# nRF24L01.net
KiCad netlist of a schematic drawn in Altium Designer
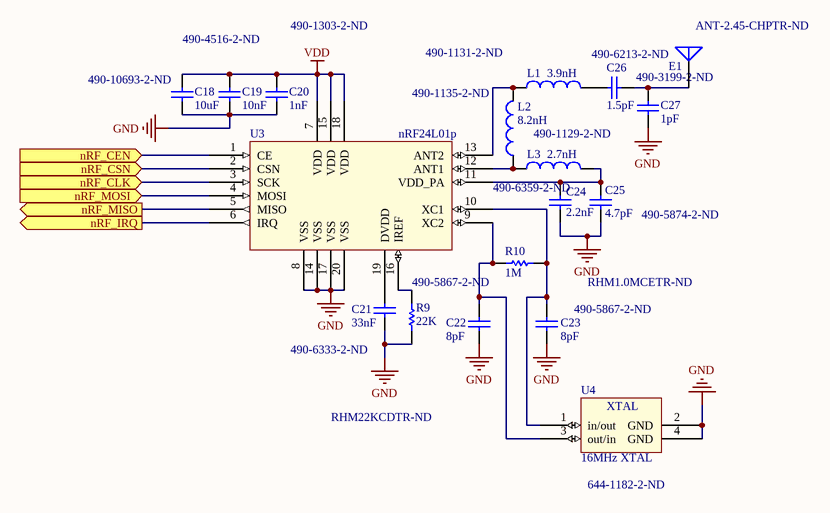
[diagram p0: nRF24L01.SchDoc]

(export (version "E")
  (design (tool "Eeschema 10.0.6"))
  (components
    (comp (ref "C18")
      (value "10uF")
      (footprint "0402")
      (description "Capacitor (Semiconductor SIM Model)")
      (fields
        (field (name "SUPPLIER PART NUMBER 1") "490-10693-2-ND")
        (field (name "PUBLISHER") "Altium Limited")
      )
      (libsource (lib "Miscellaneous Devices") (part "Cap Semi"))
    )
    (comp (ref "C19")
      (value "10nF")
      (footprint "0402")
      (description "Capacitor (Semiconductor SIM Model)")
      (fields
        (field (name "SUPPLIER PART NUMBER 1") "490-4516-2-ND")
        (field (name "PUBLISHER") "Altium Limited")
      )
      (libsource (lib "Miscellaneous Devices") (part "Cap Semi"))
    )
    (comp (ref "C20")
      (value "1nF")
      (footprint "0402")
      (description "Capacitor (Semiconductor SIM Model)")
      (fields
        (field (name "SUPPLIER PART NUMBER 1") "490-1303-2-ND")
        (field (name "PUBLISHER") "Altium Limited")
      )
      (libsource (lib "Miscellaneous Devices") (part "Cap Semi"))
    )
    (comp (ref "C21")
      (value "33nF")
      (footprint "0402")
      (description "Capacitor (Semiconductor SIM Model)")
      (fields
        (field (name "SUPPLIER PART NUMBER 1") "490-6333-2-ND")
        (field (name "PUBLISHER") "Altium Limited")
      )
      (libsource (lib "Miscellaneous Devices") (part "Cap Semi"))
    )
    (comp (ref "C22")
      (value "8pF")
      (footprint "0402")
      (description "Capacitor (Semiconductor SIM Model)")
      (fields
        (field (name "SUPPLIER PART NUMBER 1") "490-5867-2-ND")
        (field (name "PUBLISHER") "Altium Limited")
      )
      (libsource (lib "Miscellaneous Devices") (part "Cap Semi"))
    )
    (comp (ref "C23")
      (value "8pF")
      (footprint "0402")
      (description "Capacitor (Semiconductor SIM Model)")
      (fields
        (field (name "SUPPLIER PART NUMBER 1") "490-5867-2-ND")
        (field (name "PUBLISHER") "Altium Limited")
      )
      (libsource (lib "Miscellaneous Devices") (part "Cap Semi"))
    )
    (comp (ref "C24")
      (value "2.2nF")
      (footprint "0402")
      (description "Capacitor (Semiconductor SIM Model)")
      (fields
        (field (name "SUPPLIER PART NUMBER 1") "490-6359-2-ND")
        (field (name "PUBLISHER") "Altium Limited")
      )
      (libsource (lib "Miscellaneous Devices") (part "Cap Semi"))
    )
    (comp (ref "C25")
      (value "4.7pF")
      (footprint "0402")
      (description "Capacitor (Semiconductor SIM Model)")
      (fields
        (field (name "SUPPLIER PART NUMBER 1") "490-5874-2-ND")
        (field (name "PUBLISHER") "Altium Limited")
      )
      (libsource (lib "Miscellaneous Devices") (part "Cap Semi"))
    )
    (comp (ref "C26")
      (value "1.5pF")
      (footprint "0402")
      (description "Capacitor (Semiconductor SIM Model)")
      (fields
        (field (name "SUPPLIER PART NUMBER 1") "490-6213-2-ND")
        (field (name "PUBLISHER") "Altium Limited")
      )
      (libsource (lib "Miscellaneous Devices") (part "Cap Semi"))
    )
    (comp (ref "C27")
      (value "1pF")
      (footprint "0402")
      (description "Capacitor (Semiconductor SIM Model)")
      (fields
        (field (name "SUPPLIER PART NUMBER 1") "490-3199-2-ND")
        (field (name "PUBLISHER") "Altium Limited")
      )
      (libsource (lib "Miscellaneous Devices") (part "Cap Semi"))
    )
    (comp (ref "E1")
      (value "~")
      (footprint "ANT-2.45-CHP-B")
      (description "Generic Antenna")
      (fields
        (field (name "SUPPLIER PART NUMBER 1") "ANT-2.45-CHPTR-ND")
        (field (name "PUBLISHER") "Altium Limited")
      )
      (libsource (lib "Miscellaneous Devices") (part "Antenna"))
    )
    (comp (ref "L1")
      (value "3.9nH")
      (footprint "0402")
      (description "Inductor")
      (fields
        (field (name "SUPPLIER PART NUMBER 1") "490-1131-2-ND")
        (field (name "PUBLISHER") "Altium Limited")
      )
      (libsource (lib "Miscellaneous Devices") (part "Inductor"))
    )
    (comp (ref "L2")
      (value "8.2nH")
      (footprint "0402")
      (description "Inductor")
      (fields
        (field (name "SUPPLIER PART NUMBER 1") "490-1135-2-ND")
        (field (name "PUBLISHER") "Altium Limited")
      )
      (libsource (lib "Miscellaneous Devices") (part "Inductor"))
    )
    (comp (ref "L3")
      (value "2.7nH")
      (footprint "0402")
      (description "Inductor")
      (fields
        (field (name "SUPPLIER PART NUMBER 1") "490-1129-2-ND")
        (field (name "PUBLISHER") "Altium Limited")
      )
      (libsource (lib "Miscellaneous Devices") (part "Inductor"))
    )
    (comp (ref "R9")
      (value "22K")
      (footprint "0402")
      (description "Semiconductor Resistor")
      (fields
        (field (name "SUPPLIER PART NUMBER 1") "RHM22KCDTR-ND")
        (field (name "PUBLISHER") "Altium Limited")
      )
      (libsource (lib "Miscellaneous Devices") (part "Res Semi"))
    )
    (comp (ref "R10")
      (value "1M")
      (footprint "0402")
      (description "Semiconductor Resistor")
      (fields
        (field (name "SUPPLIER PART NUMBER 1") "RHM1.0MCETR-ND")
        (field (name "PUBLISHER") "Altium Limited")
      )
      (libsource (lib "Miscellaneous Devices") (part "Res Semi"))
    )
    (comp (ref "U3")
      (value "nRF24L01p")
      (footprint "Component_nRF")
      (libsource (lib "nRF24L01") (part "Component_nRF"))
    )
    (comp (ref "U4")
      (value "16MHz XTAL")
      (footprint "8Y-16.000MAAV-T")
      (description "SMD 16 MHz XTAL")
      (fields (field (name "SUPPLIER PART NUMBER 1") "644-1182-2-ND"))
      (libsource (lib "headstage_parts") (part "8Y-16.000MAAV-T"))
    )
  )
  (nets
    (net (code "1") (name "/nRF_CEN") (class "Default")
      (node (ref "U3") (pin "1") (pinfunction "CE_1") (pintype "input"))
    )
    (net (code "2") (name "/nRF_CLK") (class "Default")
      (node (ref "U3") (pin "3") (pinfunction "SCK_3") (pintype "input"))
    )
    (net (code "3") (name "/nRF_CSN") (class "Default")
      (node (ref "U3") (pin "2") (pinfunction "CSN_2") (pintype "input"))
    )
    (net (code "4") (name "/nRF_IRQ") (class "Default")
      (node (ref "U3") (pin "6") (pinfunction "IRQ_6") (pintype "output"))
    )
    (net (code "5") (name "/nRF_MISO") (class "Default")
      (node (ref "U3") (pin "5") (pinfunction "MISO_5") (pintype "output"))
    )
    (net (code "6") (name "/nRF_MOSI") (class "Default")
      (node (ref "U3") (pin "4") (pinfunction "MOSI_4") (pintype "input"))
    )
    (net (code "7") (name "GND") (class "Default")
      (node (ref "C18") (pin "1") (pinfunction "1_1") (pintype "passive"))
      (node (ref "C19") (pin "1") (pinfunction "1_1") (pintype "passive"))
      (node (ref "C20") (pin "1") (pinfunction "1_1") (pintype "passive"))
      (node (ref "C21") (pin "1") (pinfunction "1_1") (pintype "passive"))
      (node (ref "C22") (pin "1") (pinfunction "1_1") (pintype "passive"))
      (node (ref "C23") (pin "1") (pinfunction "1_1") (pintype "passive"))
      (node (ref "C24") (pin "1") (pinfunction "1_1") (pintype "passive"))
      (node (ref "C25") (pin "1") (pinfunction "1_1") (pintype "passive"))
      (node (ref "C27") (pin "2") (pinfunction "2_2") (pintype "passive"))
      (node (ref "R9") (pin "1") (pinfunction "1_1") (pintype "passive"))
      (node (ref "U3") (pin "14") (pinfunction "VSS_14") (pintype "power_in"))
      (node (ref "U3") (pin "17") (pinfunction "VSS_17") (pintype "power_in"))
      (node (ref "U3") (pin "20") (pinfunction "VSS_20") (pintype "power_in"))
      (node (ref "U3") (pin "8") (pinfunction "VSS_8") (pintype "power_in"))
      (node (ref "U4") (pin "2") (pinfunction "GND_2") (pintype "power_in"))
      (node (ref "U4") (pin "4") (pinfunction "GND_4") (pintype "power_in"))
    )
    (net (code "8") (name "Net-(C26-Pad2)") (class "Default")
      (node (ref "C26") (pin "2") (pinfunction "2_2") (pintype "passive"))
      (node (ref "L1") (pin "2") (pinfunction "2_2") (pintype "passive"))
    )
    (net (code "9") (name "Net-(E1-A)") (class "Default")
      (node (ref "C26") (pin "1") (pinfunction "1_1") (pintype "passive"))
      (node (ref "C27") (pin "1") (pinfunction "1_1") (pintype "passive"))
      (node (ref "E1") (pin "1") (pinfunction "A_1") (pintype "passive"))
    )
    (net (code "10") (name "Net-(U3-ANT1)") (class "Default")
      (node (ref "L2") (pin "1") (pinfunction "1_1") (pintype "passive"))
      (node (ref "L3") (pin "1") (pinfunction "1_1") (pintype "passive"))
      (node (ref "U3") (pin "12") (pinfunction "ANT1_12") (pintype "bidirectional"))
    )
    (net (code "11") (name "Net-(U3-ANT2)") (class "Default")
      (node (ref "L1") (pin "1") (pinfunction "1_1") (pintype "passive"))
      (node (ref "L2") (pin "2") (pinfunction "2_2") (pintype "passive"))
      (node (ref "U3") (pin "13") (pinfunction "ANT2_13") (pintype "bidirectional"))
    )
    (net (code "12") (name "Net-(U3-DVDD)") (class "Default")
      (node (ref "C21") (pin "2") (pinfunction "2_2") (pintype "passive"))
      (node (ref "U3") (pin "19") (pinfunction "DVDD_19") (pintype "power_in"))
    )
    (net (code "13") (name "Net-(U3-IREF)") (class "Default")
      (node (ref "R9") (pin "2") (pinfunction "2_2") (pintype "passive"))
      (node (ref "U3") (pin "16") (pinfunction "IREF_16") (pintype "bidirectional"))
    )
    (net (code "14") (name "Net-(U3-VDD_PA)") (class "Default")
      (node (ref "C24") (pin "2") (pinfunction "2_2") (pintype "passive"))
      (node (ref "C25") (pin "2") (pinfunction "2_2") (pintype "passive"))
      (node (ref "L3") (pin "2") (pinfunction "2_2") (pintype "passive"))
      (node (ref "U3") (pin "11") (pinfunction "VDD_PA_11") (pintype "bidirectional"))
    )
    (net (code "15") (name "Net-(U3-XC1)") (class "Default")
      (node (ref "C23") (pin "2") (pinfunction "2_2") (pintype "passive"))
      (node (ref "R10") (pin "1") (pinfunction "1_1") (pintype "passive"))
      (node (ref "U3") (pin "10") (pinfunction "XC1_10") (pintype "bidirectional"))
      (node (ref "U4") (pin "1") (pinfunction "in/out_1") (pintype "bidirectional"))
    )
    (net (code "16") (name "Net-(U3-XC2)") (class "Default")
      (node (ref "C22") (pin "2") (pinfunction "2_2") (pintype "passive"))
      (node (ref "R10") (pin "2") (pinfunction "2_2") (pintype "passive"))
      (node (ref "U3") (pin "9") (pinfunction "XC2_9") (pintype "bidirectional"))
      (node (ref "U4") (pin "3") (pinfunction "out/in_3") (pintype "bidirectional"))
    )
    (net (code "17") (name "VDD") (class "Default")
      (node (ref "C18") (pin "2") (pinfunction "2_2") (pintype "passive"))
      (node (ref "C19") (pin "2") (pinfunction "2_2") (pintype "passive"))
      (node (ref "C20") (pin "2") (pinfunction "2_2") (pintype "passive"))
      (node (ref "U3") (pin "15") (pinfunction "VDD_15") (pintype "power_in"))
      (node (ref "U3") (pin "18") (pinfunction "VDD_18") (pintype "power_in"))
      (node (ref "U3") (pin "7") (pinfunction "VDD_7") (pintype "power_in"))
    )
  )
)
